# ezlpc-proto.net
KiCad netlist of a schematic drawn in EAGLE
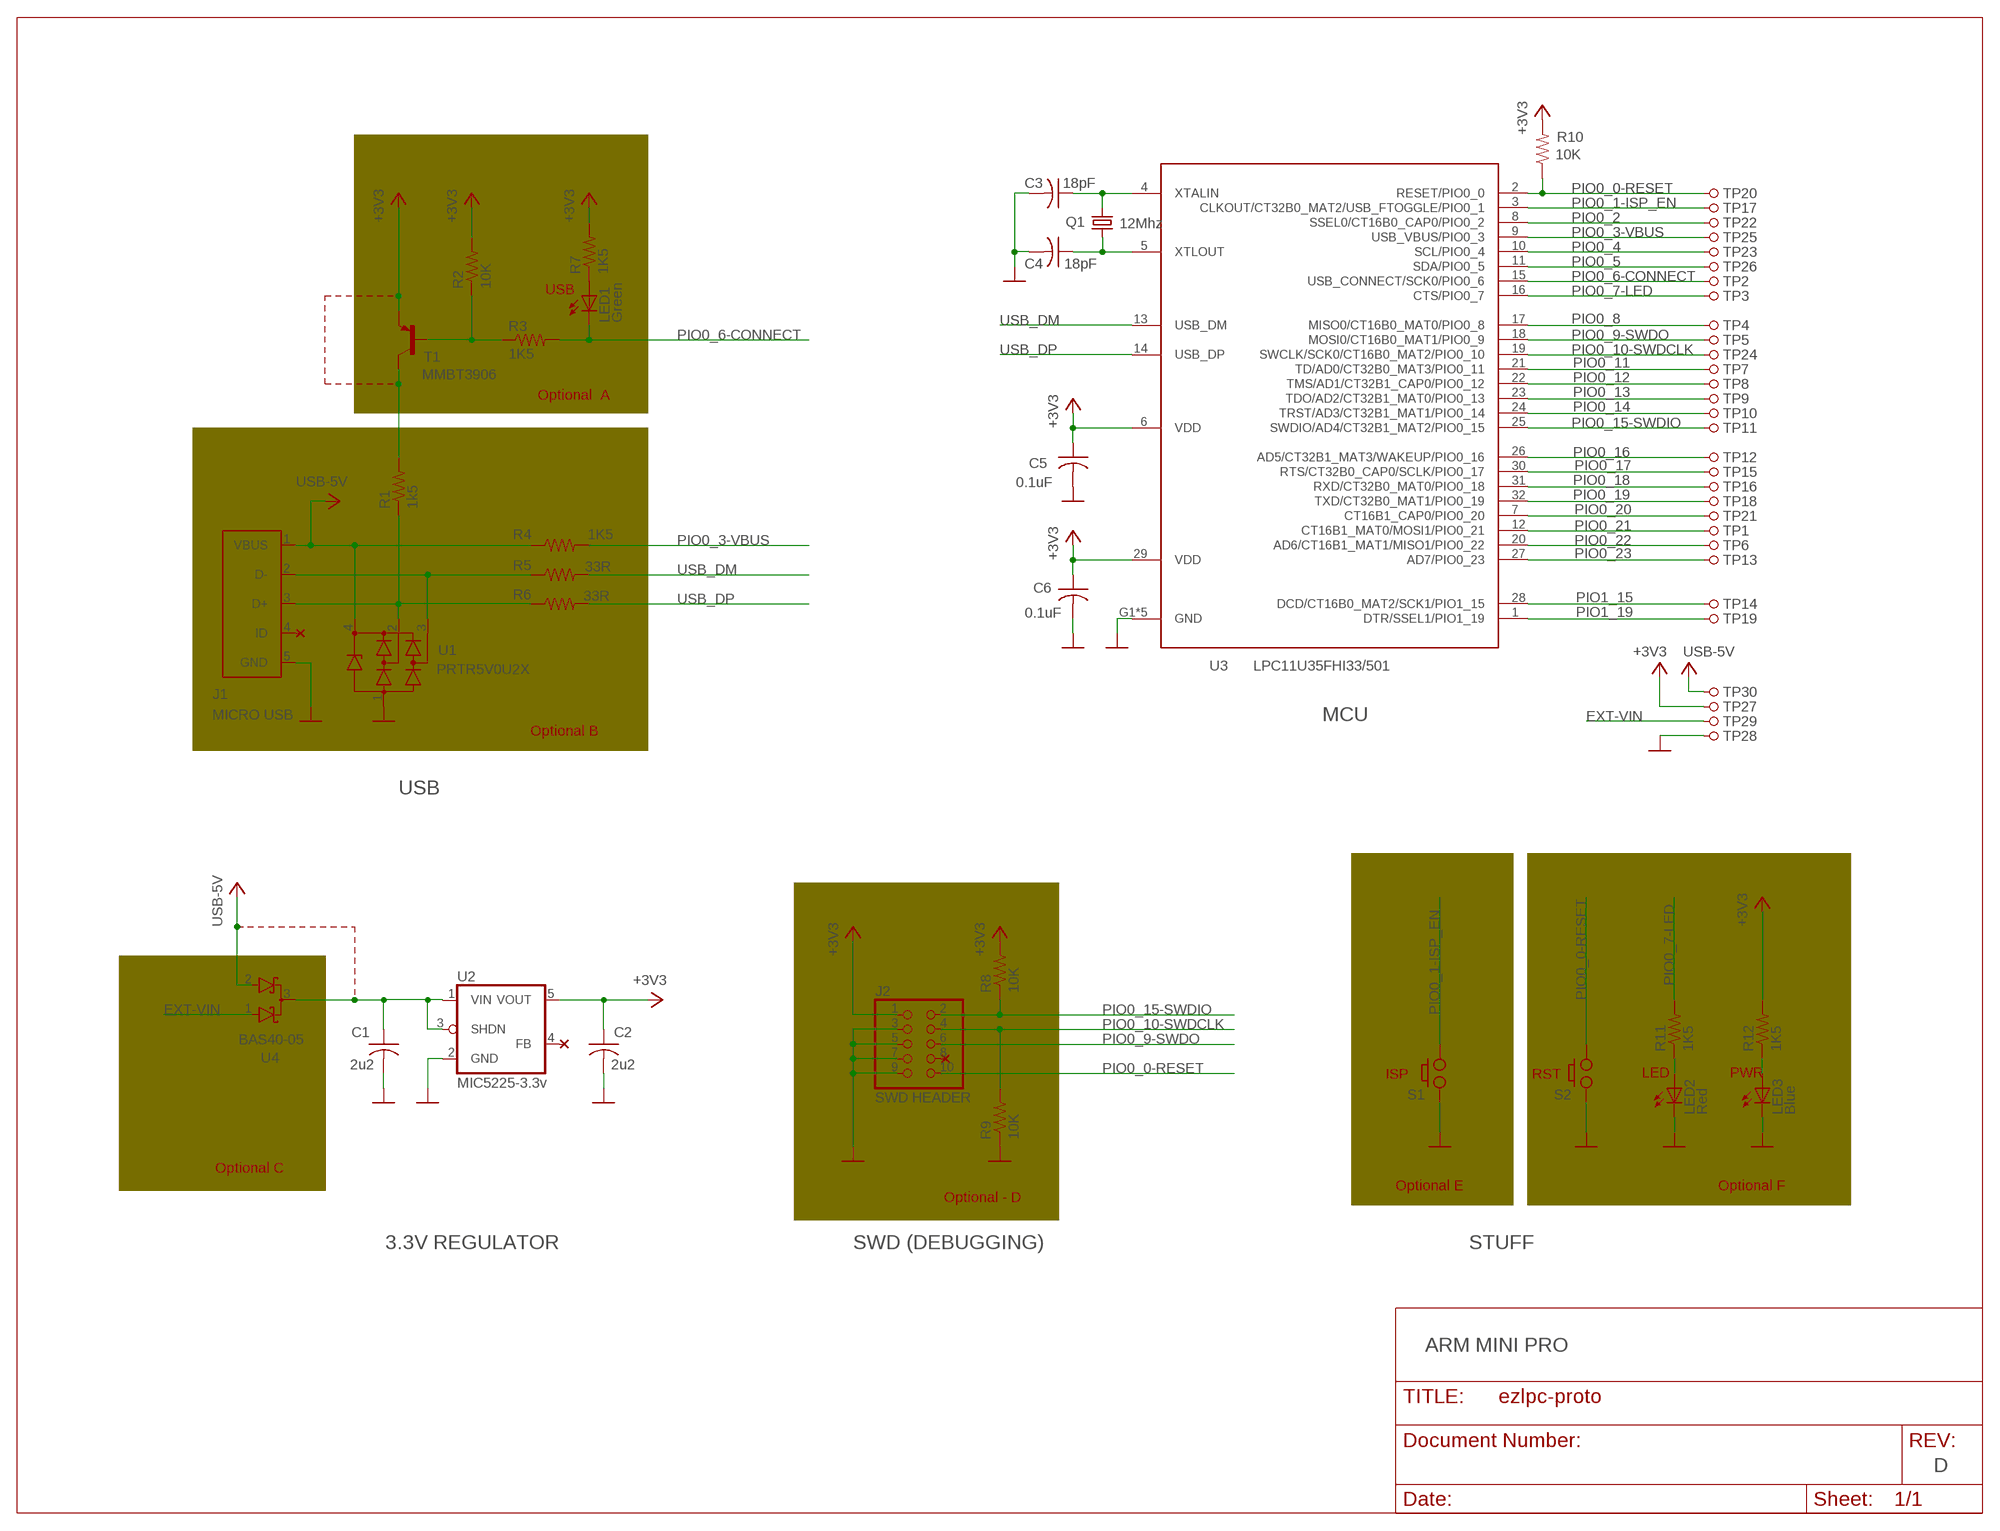
[diagram p0: schematic, sheet 1]

(export (version "E")
  (design (tool "Eeschema 10.0.6"))
  (components
    (comp (ref "C1")
      (value "2u2")
      (footprint "eagle-import:C0603K")
      (libsource (lib "eagle-import") (part "CAPACITORC0603K"))
    )
    (comp (ref "C2")
      (value "2u2")
      (footprint "eagle-import:C0603K")
      (libsource (lib "eagle-import") (part "CAPACITORC0603K"))
    )
    (comp (ref "C3")
      (value "18pF")
      (footprint "eagle-import:C0402K")
      (libsource (lib "eagle-import") (part "C-USC0402K"))
    )
    (comp (ref "C4")
      (value "18pF")
      (footprint "eagle-import:C0402K")
      (libsource (lib "eagle-import") (part "C-USC0402K"))
    )
    (comp (ref "C5")
      (value "0.1uF")
      (footprint "eagle-import:C0603K")
      (libsource (lib "eagle-import") (part "CAPACITORC0603K"))
    )
    (comp (ref "C6")
      (value "0.1uF")
      (footprint "eagle-import:C0603K")
      (libsource (lib "eagle-import") (part "CAPACITORC0603K"))
    )
    (comp (ref "J1")
      (value "MICRO USB")
      (footprint "eagle-import:USB-MICRO-ZX62RD-AB-5P8")
      (libsource (lib "eagle-import") (part "USB"))
    )
    (comp (ref "J2")
      (value "SWD HEADER")
      (footprint "eagle-import:SWD-HEADER")
      (libsource (lib "eagle-import") (part "SWD-HEADER"))
    )
    (comp (ref "LED1")
      (value "Green")
      (footprint "eagle-import:CHIP-LED0603")
      (libsource (lib "eagle-import") (part "LEDCHIP-LED0603"))
    )
    (comp (ref "LED2")
      (value "Red")
      (footprint "eagle-import:CHIP-LED0603")
      (libsource (lib "eagle-import") (part "LEDCHIP-LED0603"))
    )
    (comp (ref "LED3")
      (value "Blue")
      (footprint "eagle-import:CHIP-LED0603")
      (libsource (lib "eagle-import") (part "LEDCHIP-LED0603"))
    )
    (comp (ref "Q1")
      (value "12Mhz")
      (footprint "eagle-import:CRYSTAL")
      (libsource (lib "eagle-import") (part "CRYSTALCTS406"))
    )
    (comp (ref "R1")
      (value "1k5")
      (footprint "eagle-import:R0402")
      (libsource (lib "eagle-import") (part "R-US_R0402"))
    )
    (comp (ref "R2")
      (value "10K")
      (footprint "eagle-import:R0402")
      (libsource (lib "eagle-import") (part "R-US_R0402"))
    )
    (comp (ref "R3")
      (value "1K5")
      (footprint "eagle-import:R0402")
      (libsource (lib "eagle-import") (part "R-US_R0402"))
    )
    (comp (ref "R4")
      (value "1K5")
      (footprint "eagle-import:R0402")
      (libsource (lib "eagle-import") (part "R-US_R0402"))
    )
    (comp (ref "R5")
      (value "33R")
      (footprint "eagle-import:R0402")
      (libsource (lib "eagle-import") (part "R-US_R0402"))
    )
    (comp (ref "R6")
      (value "33R")
      (footprint "eagle-import:R0402")
      (libsource (lib "eagle-import") (part "R-US_R0402"))
    )
    (comp (ref "R7")
      (value "1K5")
      (footprint "eagle-import:R0402")
      (libsource (lib "eagle-import") (part "R-US_R0402"))
    )
    (comp (ref "R8")
      (value "10K")
      (footprint "eagle-import:R0402")
      (libsource (lib "eagle-import") (part "R-US_R0402"))
    )
    (comp (ref "R9")
      (value "10K")
      (footprint "eagle-import:R0402")
      (libsource (lib "eagle-import") (part "R-US_R0402"))
    )
    (comp (ref "R10")
      (value "10K")
      (footprint "eagle-import:R0402")
      (libsource (lib "eagle-import") (part "R-US_R0402"))
    )
    (comp (ref "R11")
      (value "1K5")
      (footprint "eagle-import:R0402")
      (libsource (lib "eagle-import") (part "R-US_R0402"))
    )
    (comp (ref "R12")
      (value "1K5")
      (footprint "eagle-import:R0402")
      (libsource (lib "eagle-import") (part "R-US_R0402"))
    )
    (comp (ref "S1")
      (value "PUSH_BUTTON")
      (footprint "eagle-import:PUSH_BUTTON")
      (libsource (lib "eagle-import") (part "PUSH_BUTTON"))
    )
    (comp (ref "S2")
      (value "PUSH_BUTTON")
      (footprint "eagle-import:PUSH_BUTTON")
      (libsource (lib "eagle-import") (part "PUSH_BUTTON"))
    )
    (comp (ref "T1")
      (value "MMBT3906")
      (footprint "eagle-import:SOT23-BEC")
      (libsource (lib "eagle-import") (part "-PNP-SOT23-BECBC857B"))
    )
    (comp (ref "TP1")
      (value "HDR1")
      (footprint "eagle-import:1X01-SQUARE")
      (libsource (lib "eagle-import") (part "PINHD-1X1SQUARE"))
    )
    (comp (ref "TP2")
      (value "HDR1")
      (footprint "eagle-import:1X01")
      (libsource (lib "eagle-import") (part "PINHD-1X1"))
    )
    (comp (ref "TP3")
      (value "HDR1")
      (footprint "eagle-import:1X01")
      (libsource (lib "eagle-import") (part "PINHD-1X1"))
    )
    (comp (ref "TP4")
      (value "HDR1")
      (footprint "eagle-import:1X01")
      (libsource (lib "eagle-import") (part "PINHD-1X1"))
    )
    (comp (ref "TP5")
      (value "HDR1")
      (footprint "eagle-import:1X01")
      (libsource (lib "eagle-import") (part "PINHD-1X1"))
    )
    (comp (ref "TP6")
      (value "HDR1")
      (footprint "eagle-import:1X01")
      (libsource (lib "eagle-import") (part "PINHD-1X1"))
    )
    (comp (ref "TP7")
      (value "HDR1")
      (footprint "eagle-import:1X01")
      (libsource (lib "eagle-import") (part "PINHD-1X1"))
    )
    (comp (ref "TP8")
      (value "HDR1")
      (footprint "eagle-import:1X01")
      (libsource (lib "eagle-import") (part "PINHD-1X1"))
    )
    (comp (ref "TP9")
      (value "HDR1")
      (footprint "eagle-import:1X01")
      (libsource (lib "eagle-import") (part "PINHD-1X1"))
    )
    (comp (ref "TP10")
      (value "HDR1")
      (footprint "eagle-import:1X01")
      (libsource (lib "eagle-import") (part "PINHD-1X1"))
    )
    (comp (ref "TP11")
      (value "HDR1")
      (footprint "eagle-import:1X01")
      (libsource (lib "eagle-import") (part "PINHD-1X1"))
    )
    (comp (ref "TP12")
      (value "HDR1")
      (footprint "eagle-import:1X01")
      (libsource (lib "eagle-import") (part "PINHD-1X1"))
    )
    (comp (ref "TP13")
      (value "HDR1")
      (footprint "eagle-import:1X01")
      (libsource (lib "eagle-import") (part "PINHD-1X1"))
    )
    (comp (ref "TP14")
      (value "HDR1")
      (footprint "eagle-import:1X01")
      (libsource (lib "eagle-import") (part "PINHD-1X1"))
    )
    (comp (ref "TP15")
      (value "HDR1")
      (footprint "eagle-import:1X01")
      (libsource (lib "eagle-import") (part "PINHD-1X1"))
    )
    (comp (ref "TP16")
      (value "HDR1")
      (footprint "eagle-import:1X01")
      (libsource (lib "eagle-import") (part "PINHD-1X1"))
    )
    (comp (ref "TP17")
      (value "HDR1")
      (footprint "eagle-import:1X01")
      (libsource (lib "eagle-import") (part "PINHD-1X1"))
    )
    (comp (ref "TP18")
      (value "HDR1")
      (footprint "eagle-import:1X01")
      (libsource (lib "eagle-import") (part "PINHD-1X1"))
    )
    (comp (ref "TP19")
      (value "HDR1")
      (footprint "eagle-import:1X01")
      (libsource (lib "eagle-import") (part "PINHD-1X1"))
    )
    (comp (ref "TP20")
      (value "HDR1")
      (footprint "eagle-import:1X01")
      (libsource (lib "eagle-import") (part "PINHD-1X1"))
    )
    (comp (ref "TP21")
      (value "HDR1")
      (footprint "eagle-import:1X01")
      (libsource (lib "eagle-import") (part "PINHD-1X1"))
    )
    (comp (ref "TP22")
      (value "HDR1")
      (footprint "eagle-import:1X01")
      (libsource (lib "eagle-import") (part "PINHD-1X1"))
    )
    (comp (ref "TP23")
      (value "HDR1")
      (footprint "eagle-import:1X01")
      (libsource (lib "eagle-import") (part "PINHD-1X1"))
    )
    (comp (ref "TP24")
      (value "HDR1")
      (footprint "eagle-import:1X01")
      (libsource (lib "eagle-import") (part "PINHD-1X1"))
    )
    (comp (ref "TP25")
      (value "HDR1")
      (footprint "eagle-import:1X01")
      (libsource (lib "eagle-import") (part "PINHD-1X1"))
    )
    (comp (ref "TP26")
      (value "HDR1")
      (footprint "eagle-import:1X01")
      (libsource (lib "eagle-import") (part "PINHD-1X1"))
    )
    (comp (ref "TP27")
      (value "HDR1")
      (footprint "eagle-import:1X01")
      (libsource (lib "eagle-import") (part "PINHD-1X1"))
    )
    (comp (ref "TP28")
      (value "HDR1")
      (footprint "eagle-import:1X01")
      (libsource (lib "eagle-import") (part "PINHD-1X1"))
    )
    (comp (ref "TP29")
      (value "HDR1")
      (footprint "eagle-import:1X01")
      (libsource (lib "eagle-import") (part "PINHD-1X1"))
    )
    (comp (ref "TP30")
      (value "HDR1")
      (footprint "eagle-import:1X01")
      (libsource (lib "eagle-import") (part "PINHD-1X1"))
    )
    (comp (ref "U1")
      (value "PRTR5V0U2X")
      (footprint "eagle-import:SOT143B")
      (libsource (lib "eagle-import") (part "PRTR5V0U2X"))
    )
    (comp (ref "U2")
      (value "MIC5225-3.3v")
      (footprint "eagle-import:SOT25")
      (libsource (lib "eagle-import") (part "TC1015"))
    )
    (comp (ref "U3")
      (value "LPC11U35FHI33/501")
      (footprint "eagle-import:HVQFN33-5MM")
      (libsource (lib "eagle-import") (part "LPC11U35FHN33/501"))
    )
    (comp (ref "U4")
      (value "BAS40-05")
      (footprint "eagle-import:SOT23")
      (libsource (lib "eagle-import") (part "BAS40-05"))
    )
  )
  (nets
    (net (code "1") (name "+3V3") (class "Default")
      (node (ref "C2") (pin "1") (pinfunction "1_1") (pintype "passive"))
      (node (ref "C5") (pin "1") (pinfunction "1_1") (pintype "passive"))
      (node (ref "C6") (pin "1") (pinfunction "1_1") (pintype "passive"))
      (node (ref "J2") (pin "1") (pinfunction "1_1") (pintype "passive"))
      (node (ref "R10") (pin "2") (pinfunction "2_2") (pintype "passive"))
      (node (ref "R12") (pin "2") (pinfunction "2_2") (pintype "passive"))
      (node (ref "R2") (pin "2") (pinfunction "2_2") (pintype "passive"))
      (node (ref "R7") (pin "2") (pinfunction "2_2") (pintype "passive"))
      (node (ref "R8") (pin "2") (pinfunction "2_2") (pintype "passive"))
      (node (ref "T1") (pin "E") (pinfunction "E_E") (pintype "passive"))
      (node (ref "TP27") (pin "1") (pinfunction "1_1") (pintype "passive"))
      (node (ref "U2") (pin "5") (pinfunction "VOUT_5") (pintype "power_in"))
      (node (ref "U3") (pin "29") (pinfunction "VDD_29") (pintype "bidirectional"))
      (node (ref "U3") (pin "6") (pinfunction "VDD_6") (pintype "bidirectional"))
    )
    (net (code "2") (name "/EXT-VIN") (class "Default")
      (node (ref "TP29") (pin "1") (pinfunction "1_1") (pintype "passive"))
      (node (ref "U4") (pin "1") (pinfunction "A1_1") (pintype "passive"))
    )
    (net (code "3") (name "/PIO0_0-RESET") (class "Default")
      (node (ref "J2") (pin "10") (pinfunction "10_10") (pintype "passive"))
      (node (ref "R10") (pin "1") (pinfunction "1_1") (pintype "passive"))
      (node (ref "S2") (pin "B2") (pinfunction "2_B2") (pintype "passive"))
      (node (ref "TP20") (pin "1") (pinfunction "1_1") (pintype "passive"))
      (node (ref "U3") (pin "2") (pinfunction "RESET/PIO0_0_2") (pintype "bidirectional"))
    )
    (net (code "4") (name "/PIO0_1-ISP_EN") (class "Default")
      (node (ref "S1") (pin "B2") (pinfunction "2_B2") (pintype "passive"))
      (node (ref "TP17") (pin "1") (pinfunction "1_1") (pintype "passive"))
      (node (ref "U3") (pin "3") (pinfunction "CLKOUT/CT32B0_MAT2/USB_FTOGGLE/PIO0_1_3") (pintype "bidirectional"))
    )
    (net (code "5") (name "/PIO0_2") (class "Default")
      (node (ref "TP22") (pin "1") (pinfunction "1_1") (pintype "passive"))
      (node (ref "U3") (pin "8") (pinfunction "SSEL0/CT16B0_CAP0/PIO0_2_8") (pintype "bidirectional"))
    )
    (net (code "6") (name "/PIO0_3-VBUS") (class "Default")
      (node (ref "R4") (pin "2") (pinfunction "2_2") (pintype "passive"))
      (node (ref "TP25") (pin "1") (pinfunction "1_1") (pintype "passive"))
      (node (ref "U3") (pin "9") (pinfunction "USB_VBUS/PIO0_3_9") (pintype "bidirectional"))
    )
    (net (code "7") (name "/PIO0_4") (class "Default")
      (node (ref "TP23") (pin "1") (pinfunction "1_1") (pintype "passive"))
      (node (ref "U3") (pin "10") (pinfunction "SCL/PIO0_4_10") (pintype "bidirectional"))
    )
    (net (code "8") (name "/PIO0_5") (class "Default")
      (node (ref "TP26") (pin "1") (pinfunction "1_1") (pintype "passive"))
      (node (ref "U3") (pin "11") (pinfunction "SDA/PIO0_5_11") (pintype "bidirectional"))
    )
    (net (code "9") (name "/PIO0_6-CONNECT") (class "Default")
      (node (ref "LED1") (pin "C") (pinfunction "C_C") (pintype "passive"))
      (node (ref "R3") (pin "2") (pinfunction "2_2") (pintype "passive"))
      (node (ref "TP2") (pin "1") (pinfunction "1_1") (pintype "passive"))
      (node (ref "U3") (pin "15") (pinfunction "USB_CONNECT/SCK0/PIO0_6_15") (pintype "bidirectional"))
    )
    (net (code "10") (name "/PIO0_7-LED") (class "Default")
      (node (ref "R11") (pin "2") (pinfunction "2_2") (pintype "passive"))
      (node (ref "TP3") (pin "1") (pinfunction "1_1") (pintype "passive"))
      (node (ref "U3") (pin "16") (pinfunction "CTS/PIO0_7_16") (pintype "bidirectional"))
    )
    (net (code "11") (name "/PIO0_8") (class "Default")
      (node (ref "TP4") (pin "1") (pinfunction "1_1") (pintype "passive"))
      (node (ref "U3") (pin "17") (pinfunction "MISO0/CT16B0_MAT0/PIO0_8_17") (pintype "bidirectional"))
    )
    (net (code "12") (name "/PIO0_9-SWDO") (class "Default")
      (node (ref "J2") (pin "6") (pinfunction "6_6") (pintype "passive"))
      (node (ref "TP5") (pin "1") (pinfunction "1_1") (pintype "passive"))
      (node (ref "U3") (pin "18") (pinfunction "MOSI0/CT16B0_MAT1/PIO0_9_18") (pintype "bidirectional"))
    )
    (net (code "13") (name "/PIO0_10-SWDCLK") (class "Default")
      (node (ref "J2") (pin "4") (pinfunction "4_4") (pintype "passive"))
      (node (ref "R9") (pin "2") (pinfunction "2_2") (pintype "passive"))
      (node (ref "TP24") (pin "1") (pinfunction "1_1") (pintype "passive"))
      (node (ref "U3") (pin "19") (pinfunction "SWCLK/SCK0/CT16B0_MAT2/PIO0_10_19") (pintype "bidirectional"))
    )
    (net (code "14") (name "/PIO0_11") (class "Default")
      (node (ref "TP7") (pin "1") (pinfunction "1_1") (pintype "passive"))
      (node (ref "U3") (pin "21") (pinfunction "TD/AD0/CT32B0_MAT3/PIO0_11_21") (pintype "bidirectional"))
    )
    (net (code "15") (name "/PIO0_12") (class "Default")
      (node (ref "TP8") (pin "1") (pinfunction "1_1") (pintype "passive"))
      (node (ref "U3") (pin "22") (pinfunction "TMS/AD1/CT32B1_CAP0/PIO0_12_22") (pintype "bidirectional"))
    )
    (net (code "16") (name "/PIO0_13") (class "Default")
      (node (ref "TP9") (pin "1") (pinfunction "1_1") (pintype "passive"))
      (node (ref "U3") (pin "23") (pinfunction "TDO/AD2/CT32B1_MAT0/PIO0_13_23") (pintype "bidirectional"))
    )
    (net (code "17") (name "/PIO0_14") (class "Default")
      (node (ref "TP10") (pin "1") (pinfunction "1_1") (pintype "passive"))
      (node (ref "U3") (pin "24") (pinfunction "TRST/AD3/CT32B1_MAT1/PIO0_14_24") (pintype "bidirectional"))
    )
    (net (code "18") (name "/PIO0_15-SWDIO") (class "Default")
      (node (ref "J2") (pin "2") (pinfunction "2_2") (pintype "passive"))
      (node (ref "R8") (pin "1") (pinfunction "1_1") (pintype "passive"))
      (node (ref "TP11") (pin "1") (pinfunction "1_1") (pintype "passive"))
      (node (ref "U3") (pin "25") (pinfunction "SWDIO/AD4/CT32B1_MAT2/PIO0_15_25") (pintype "bidirectional"))
    )
    (net (code "19") (name "/PIO0_16") (class "Default")
      (node (ref "TP12") (pin "1") (pinfunction "1_1") (pintype "passive"))
      (node (ref "U3") (pin "26") (pinfunction "AD5/CT32B1_MAT3/WAKEUP/PIO0_16_26") (pintype "bidirectional"))
    )
    (net (code "20") (name "/PIO0_17") (class "Default")
      (node (ref "TP15") (pin "1") (pinfunction "1_1") (pintype "passive"))
      (node (ref "U3") (pin "30") (pinfunction "RTS/CT32B0_CAP0/SCLK/PIO0_17_30") (pintype "bidirectional"))
    )
    (net (code "21") (name "/PIO0_18") (class "Default")
      (node (ref "TP16") (pin "1") (pinfunction "1_1") (pintype "passive"))
      (node (ref "U3") (pin "31") (pinfunction "RXD/CT32B0_MAT0/PIO0_18_31") (pintype "bidirectional"))
    )
    (net (code "22") (name "/PIO0_19") (class "Default")
      (node (ref "TP18") (pin "1") (pinfunction "1_1") (pintype "passive"))
      (node (ref "U3") (pin "32") (pinfunction "TXD/CT32B0_MAT1/PIO0_19_32") (pintype "bidirectional"))
    )
    (net (code "23") (name "/PIO0_20") (class "Default")
      (node (ref "TP21") (pin "1") (pinfunction "1_1") (pintype "passive"))
      (node (ref "U3") (pin "7") (pinfunction "CT16B1_CAP0/PIO0_20_7") (pintype "bidirectional"))
    )
    (net (code "24") (name "/PIO0_21") (class "Default")
      (node (ref "TP1") (pin "1") (pinfunction "1_1") (pintype "passive"))
      (node (ref "U3") (pin "12") (pinfunction "CT16B1_MAT0/MOSI1/PIO0_21_12") (pintype "bidirectional"))
    )
    (net (code "25") (name "/PIO0_22") (class "Default")
      (node (ref "TP6") (pin "1") (pinfunction "1_1") (pintype "passive"))
      (node (ref "U3") (pin "20") (pinfunction "AD6/CT16B1_MAT1/MISO1/PIO0_22_20") (pintype "bidirectional"))
    )
    (net (code "26") (name "/PIO0_23") (class "Default")
      (node (ref "TP13") (pin "1") (pinfunction "1_1") (pintype "passive"))
      (node (ref "U3") (pin "27") (pinfunction "AD7/PIO0_23_27") (pintype "bidirectional"))
    )
    (net (code "27") (name "/PIO1_15") (class "Default")
      (node (ref "TP14") (pin "1") (pinfunction "1_1") (pintype "passive"))
      (node (ref "U3") (pin "28") (pinfunction "DCD/CT16B0_MAT2/SCK1/PIO1_15_28") (pintype "bidirectional"))
    )
    (net (code "28") (name "/PIO1_19") (class "Default")
      (node (ref "TP19") (pin "1") (pinfunction "1_1") (pintype "passive"))
      (node (ref "U3") (pin "1") (pinfunction "DTR/SSEL1/PIO1_19_1") (pintype "bidirectional"))
    )
    (net (code "29") (name "/USB_DM") (class "Default")
      (node (ref "R5") (pin "2") (pinfunction "2_2") (pintype "passive"))
      (node (ref "U3") (pin "13") (pinfunction "USB_DM_13") (pintype "bidirectional"))
    )
    (net (code "30") (name "/USB_DP") (class "Default")
      (node (ref "R6") (pin "2") (pinfunction "2_2") (pintype "passive"))
      (node (ref "U3") (pin "14") (pinfunction "USB_DP_14") (pintype "bidirectional"))
    )
    (net (code "31") (name "GND") (class "Default")
      (node (ref "C1") (pin "2") (pinfunction "2_2") (pintype "passive"))
      (node (ref "C2") (pin "2") (pinfunction "2_2") (pintype "passive"))
      (node (ref "C3") (pin "2") (pinfunction "2_2") (pintype "passive"))
      (node (ref "C4") (pin "2") (pinfunction "2_2") (pintype "passive"))
      (node (ref "C5") (pin "2") (pinfunction "2_2") (pintype "passive"))
      (node (ref "C6") (pin "2") (pinfunction "2_2") (pintype "passive"))
      (node (ref "J1") (pin "5") (pinfunction "GND_5") (pintype "bidirectional"))
      (node (ref "J2") (pin "3") (pinfunction "3_3") (pintype "passive"))
      (node (ref "J2") (pin "5") (pinfunction "5_5") (pintype "passive"))
      (node (ref "J2") (pin "7") (pinfunction "7_7") (pintype "passive"))
      (node (ref "J2") (pin "9") (pinfunction "9_9") (pintype "passive"))
      (node (ref "LED2") (pin "C") (pinfunction "C_C") (pintype "passive"))
      (node (ref "LED3") (pin "C") (pinfunction "C_C") (pintype "passive"))
      (node (ref "R9") (pin "1") (pinfunction "1_1") (pintype "passive"))
      (node (ref "S1") (pin "A1") (pinfunction "1_A1") (pintype "passive"))
      (node (ref "S2") (pin "A1") (pinfunction "1_A1") (pintype "passive"))
      (node (ref "TP28") (pin "1") (pinfunction "1_1") (pintype "passive"))
      (node (ref "U1") (pin "1") (pinfunction "GND_1") (pintype "passive"))
      (node (ref "U2") (pin "2") (pinfunction "GND_2") (pintype "power_in"))
      (node (ref "U3") (pin "G1") (pinfunction "GND_G1") (pintype "bidirectional"))
      (node (ref "U3") (pin "G2") (pinfunction "GND_G2") (pintype "bidirectional"))
      (node (ref "U3") (pin "G3") (pinfunction "GND_G3") (pintype "bidirectional"))
      (node (ref "U3") (pin "G4") (pinfunction "GND_G4") (pintype "bidirectional"))
      (node (ref "U3") (pin "TAB") (pinfunction "GND_TAB") (pintype "bidirectional"))
    )
    (net (code "32") (name "Net-(J1-D+)") (class "Default")
      (node (ref "J1") (pin "3") (pinfunction "D+_3") (pintype "bidirectional"))
      (node (ref "R1") (pin "1") (pinfunction "1_1") (pintype "passive"))
      (node (ref "R6") (pin "1") (pinfunction "1_1") (pintype "passive"))
      (node (ref "U1") (pin "2") (pinfunction "IO1_2") (pintype "passive"))
    )
    (net (code "33") (name "Net-(J1-D-)") (class "Default")
      (node (ref "J1") (pin "2") (pinfunction "D-_2") (pintype "bidirectional"))
      (node (ref "R5") (pin "1") (pinfunction "1_1") (pintype "passive"))
      (node (ref "U1") (pin "3") (pinfunction "IO2_3") (pintype "passive"))
    )
    (net (code "34") (name "Net-(LED1-PadA)") (class "Default")
      (node (ref "LED1") (pin "A") (pinfunction "A_A") (pintype "passive"))
      (node (ref "R7") (pin "1") (pinfunction "1_1") (pintype "passive"))
    )
    (net (code "35") (name "Net-(LED2-PadA)") (class "Default")
      (node (ref "LED2") (pin "A") (pinfunction "A_A") (pintype "passive"))
      (node (ref "R11") (pin "1") (pinfunction "1_1") (pintype "passive"))
    )
    (net (code "36") (name "Net-(LED3-PadA)") (class "Default")
      (node (ref "LED3") (pin "A") (pinfunction "A_A") (pintype "passive"))
      (node (ref "R12") (pin "1") (pinfunction "1_1") (pintype "passive"))
    )
    (net (code "37") (name "Net-(Q1-2)") (class "Default")
      (node (ref "C3") (pin "1") (pinfunction "1_1") (pintype "passive"))
      (node (ref "Q1") (pin "3") (pinfunction "2_3") (pintype "passive"))
      (node (ref "U3") (pin "4") (pinfunction "XTALIN_4") (pintype "bidirectional"))
    )
    (net (code "38") (name "Net-(R1-Pad2)") (class "Default")
      (node (ref "R1") (pin "2") (pinfunction "2_2") (pintype "passive"))
      (node (ref "T1") (pin "C") (pinfunction "C_C") (pintype "passive"))
    )
    (net (code "39") (name "Net-(R2-Pad1)") (class "Default")
      (node (ref "R2") (pin "1") (pinfunction "1_1") (pintype "passive"))
      (node (ref "R3") (pin "1") (pinfunction "1_1") (pintype "passive"))
      (node (ref "T1") (pin "B") (pinfunction "B_B") (pintype "passive"))
    )
    (net (code "40") (name "Net-(U2-SHDN)") (class "Default")
      (node (ref "C1") (pin "1") (pinfunction "1_1") (pintype "passive"))
      (node (ref "U2") (pin "1") (pinfunction "VIN_1") (pintype "power_in"))
      (node (ref "U2") (pin "3") (pinfunction "SHDN_3") (pintype "input"))
      (node (ref "U4") (pin "3") (pinfunction "C_3") (pintype "passive"))
    )
    (net (code "41") (name "Net-(U3-XTLOUT)") (class "Default")
      (node (ref "C4") (pin "1") (pinfunction "1_1") (pintype "passive"))
      (node (ref "Q1") (pin "1") (pinfunction "1_1") (pintype "passive"))
      (node (ref "U3") (pin "5") (pinfunction "XTLOUT_5") (pintype "bidirectional"))
    )
    (net (code "42") (name "USB-5V") (class "Default")
      (node (ref "J1") (pin "1") (pinfunction "VBUS_1") (pintype "bidirectional"))
      (node (ref "R4") (pin "1") (pinfunction "1_1") (pintype "passive"))
      (node (ref "TP30") (pin "1") (pinfunction "1_1") (pintype "passive"))
      (node (ref "U1") (pin "4") (pinfunction "VCC_4") (pintype "passive"))
      (node (ref "U4") (pin "2") (pinfunction "A2_2") (pintype "passive"))
    )
    (net (code "43") (name "unconnected-(J1-ID-Pad4)") (class "Default")
      (node (ref "J1") (pin "4") (pinfunction "ID_4") (pintype "bidirectional"))
    )
    (net (code "44") (name "unconnected-(J2-Pad8)") (class "Default")
      (node (ref "J2") (pin "8") (pinfunction "8_8") (pintype "passive"))
    )
    (net (code "45") (name "unconnected-(U2-FB-Pad4)") (class "Default")
      (node (ref "U2") (pin "4") (pinfunction "FB_4") (pintype "input"))
    )
  )
)
